# current_integrator.net
KiCad netlist of a schematic drawn in Altium Designer
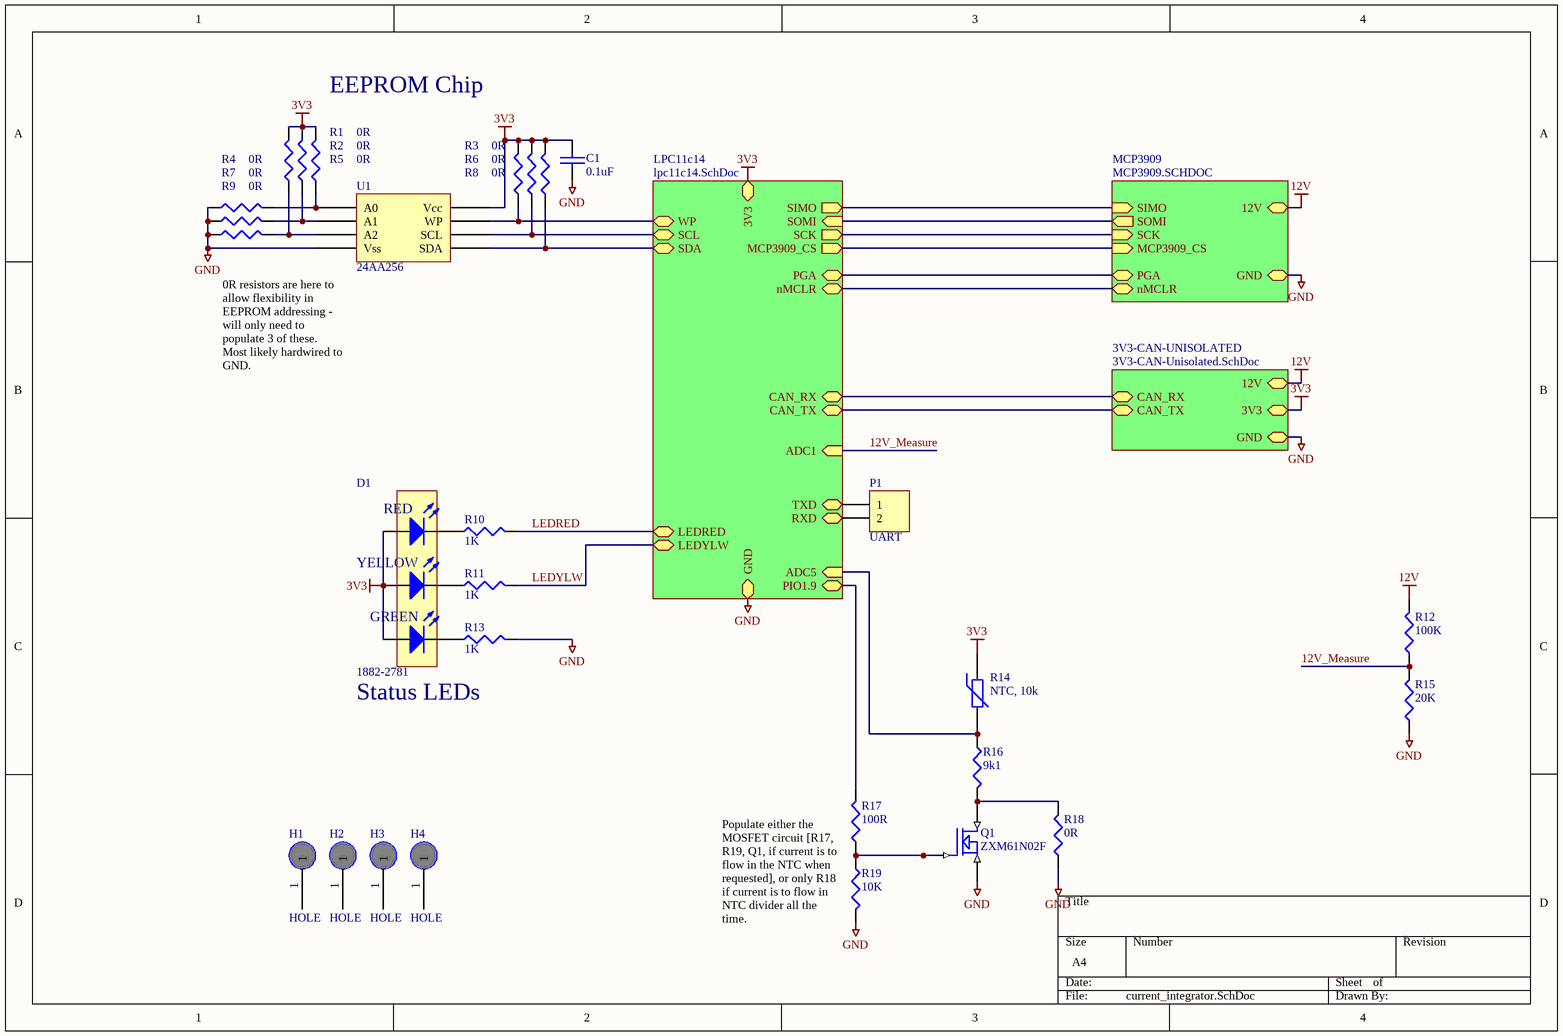
[diagram p0: current_integrator.SchDoc]

(export (version "E")
  (design (tool "Eeschema 10.0.6"))
  (components
    (comp (ref "C1")
      (value "0.1uF")
      (footprint "0805")
      (description "Capacitor")
      (libsource (lib "*") (part "CAP"))
    )
    (comp (ref "D1")
      (value "1882-2781")
      (footprint "LED_TRILEVEL")
      (description "Three level LED")
      (libsource (lib "RCLDQ") (part "LED-TRILEVEL"))
    )
    (comp (ref "H1")
      (value "HOLE")
      (footprint "M2.5")
      (description "Hole")
      (libsource (lib "Miscellaneous") (part "HOLE"))
    )
    (comp (ref "H2")
      (value "HOLE")
      (footprint "M2.5")
      (description "Hole")
      (libsource (lib "Miscellaneous") (part "HOLE"))
    )
    (comp (ref "H3")
      (value "HOLE")
      (footprint "M2.5")
      (description "Hole")
      (libsource (lib "Miscellaneous") (part "HOLE"))
    )
    (comp (ref "H4")
      (value "HOLE")
      (footprint "M2.5")
      (description "Hole")
      (libsource (lib "Miscellaneous") (part "HOLE"))
    )
    (comp (ref "P1")
      (value "UART")
      (footprint "HDR1X2")
      (description "Header, 2-Pin")
      (fields (field (name "PUBLISHER") "Altium Limited"))
      (libsource (lib "Miscellaneous Connectors") (part "Header 2"))
    )
    (comp (ref "Q1")
      (value "ZXM61N02F")
      (footprint "SOT23-3")
      (description "1.7A, 20V N-Channel Enhancement mode FET")
      (libsource (lib "RCLDQ") (part "ZXM61N02F"))
    )
    (comp (ref "R1")
      (value "0R")
      (footprint "0603")
      (description "Resistor")
      (libsource (lib "SunswiftLib20030312RR") (part "RES1"))
    )
    (comp (ref "R2")
      (value "0R")
      (footprint "0603")
      (description "Resistor")
      (libsource (lib "SunswiftLib20030312RR") (part "RES1"))
    )
    (comp (ref "R3")
      (value "0R")
      (footprint "0603")
      (description "Resistor")
      (libsource (lib "SunswiftLib20030312RR") (part "RES1"))
    )
    (comp (ref "R4")
      (value "0R")
      (footprint "0603")
      (description "Resistor")
      (libsource (lib "SunswiftLib20030312RR") (part "RES1"))
    )
    (comp (ref "R5")
      (value "0R")
      (footprint "0603")
      (description "Resistor")
      (libsource (lib "SunswiftLib20030312RR") (part "RES1"))
    )
    (comp (ref "R6")
      (value "0R")
      (footprint "0603")
      (description "Resistor")
      (libsource (lib "SunswiftLib20030312RR") (part "RES1"))
    )
    (comp (ref "R7")
      (value "0R")
      (footprint "0603")
      (description "Resistor")
      (libsource (lib "SunswiftLib20030312RR") (part "RES1"))
    )
    (comp (ref "R8")
      (value "0R")
      (footprint "0603")
      (description "Resistor")
      (libsource (lib "SunswiftLib20030312RR") (part "RES1"))
    )
    (comp (ref "R9")
      (value "0R")
      (footprint "0603")
      (description "Resistor")
      (libsource (lib "SunswiftLib20030312RR") (part "RES1"))
    )
    (comp (ref "R10")
      (value "1K")
      (footprint "0603")
      (description "Resistor")
      (libsource (lib "RCLDQ") (part "RES1"))
    )
    (comp (ref "R11")
      (value "1K")
      (footprint "0603")
      (description "Resistor")
      (libsource (lib "RCLDQ") (part "RES1"))
    )
    (comp (ref "R12")
      (value "100K")
      (footprint "1206")
      (description "Resistor")
      (libsource (lib "2009_BatteryMaster") (part "RES1"))
    )
    (comp (ref "R13")
      (value "1K")
      (footprint "0603")
      (description "Resistor")
      (libsource (lib "RCLDQ") (part "RES1"))
    )
    (comp (ref "R14")
      (value "NTC, 10k")
      (footprint "NTC_EPCOS")
      (description "Varistor (Voltage-Sensitive Resistor)")
      (libsource (lib "Miscellaneous Devices") (part "Res Varistor"))
    )
    (comp (ref "R15")
      (value "20K")
      (footprint "1206")
      (description "Resistor")
      (libsource (lib "2009_BatteryMaster") (part "RES1"))
    )
    (comp (ref "R16")
      (value "9k1")
      (footprint "0603")
      (description "Resistor")
      (libsource (lib "SUNSWIFTLIB") (part "RES1"))
    )
    (comp (ref "R17")
      (value "100R")
      (footprint "0603")
      (description "Resistor")
      (libsource (lib "SUNSWIFTLIB") (part "RES1"))
    )
    (comp (ref "R18")
      (value "0R")
      (footprint "0603")
      (description "Resistor")
      (libsource (lib "SUNSWIFTLIB") (part "RES1"))
    )
    (comp (ref "R19")
      (value "10K")
      (footprint "0603")
      (description "Resistor")
      (libsource (lib "SUNSWIFTLIB") (part "RES1"))
    )
    (comp (ref "U1") (value "24AA256") (footprint "DIP8") (libsource (lib "Miscellaneous") (part "24AA256")))
  )
  (nets
    (net (code "1") (name "/12V_Measure") (class "Default")
      (node (ref "R12") (pin "1") (pinfunction "1_1") (pintype "passive"))
      (node (ref "R15") (pin "2") (pinfunction "2_2") (pintype "passive"))
    )
    (net (code "2") (name "/ADC5") (class "Default")
      (node (ref "R14") (pin "2") (pinfunction "2_2") (pintype "passive"))
      (node (ref "R16") (pin "1") (pinfunction "1_1") (pintype "passive"))
    )
    (net (code "5") (name "/LEDRED") (class "Default")
      (node (ref "R10") (pin "2") (pinfunction "2_2") (pintype "passive"))
    )
    (net (code "6") (name "/LEDYLW") (class "Default")
      (node (ref "R11") (pin "2") (pinfunction "2_2") (pintype "passive"))
    )
    (net (code "9") (name "/PIO1.9") (class "Default")
      (node (ref "R17") (pin "2") (pinfunction "2_2") (pintype "passive"))
    )
    (net (code "10") (name "/RXD") (class "Default")
      (node (ref "P1") (pin "2") (pinfunction "2_2") (pintype "passive"))
    )
    (net (code "12") (name "/SCL") (class "Default")
      (node (ref "R6") (pin "1") (pinfunction "1_1") (pintype "passive"))
      (node (ref "U1") (pin "6") (pinfunction "SCL_6") (pintype "passive"))
    )
    (net (code "13") (name "/SDA") (class "Default")
      (node (ref "R3") (pin "1") (pinfunction "1_1") (pintype "passive"))
      (node (ref "U1") (pin "5") (pinfunction "SDA_5") (pintype "passive"))
    )
    (net (code "16") (name "/TXD") (class "Default")
      (node (ref "P1") (pin "1") (pinfunction "1_1") (pintype "passive"))
    )
    (net (code "17") (name "/WP") (class "Default")
      (node (ref "R8") (pin "1") (pinfunction "1_1") (pintype "passive"))
      (node (ref "U1") (pin "7") (pinfunction "WP_7") (pintype "passive"))
    )
    (net (code "19") (name "3V3") (class "Default")
      (node (ref "C1") (pin "1") (pinfunction "1_1") (pintype "passive"))
      (node (ref "D1") (pin "4") (pinfunction "A_4") (pintype "passive"))
      (node (ref "D1") (pin "5") (pinfunction "A_5") (pintype "passive"))
      (node (ref "D1") (pin "6") (pinfunction "A_6") (pintype "passive"))
      (node (ref "R1") (pin "2") (pinfunction "2_2") (pintype "passive"))
      (node (ref "R14") (pin "1") (pinfunction "1_1") (pintype "passive"))
      (node (ref "R2") (pin "2") (pinfunction "2_2") (pintype "passive"))
      (node (ref "R3") (pin "2") (pinfunction "2_2") (pintype "passive"))
      (node (ref "R5") (pin "2") (pinfunction "2_2") (pintype "passive"))
      (node (ref "R6") (pin "2") (pinfunction "2_2") (pintype "passive"))
      (node (ref "R8") (pin "2") (pinfunction "2_2") (pintype "passive"))
      (node (ref "U1") (pin "8") (pinfunction "Vcc_8") (pintype "passive"))
    )
    (net (code "20") (name "12V") (class "Default")
      (node (ref "R12") (pin "2") (pinfunction "2_2") (pintype "passive"))
    )
    (net (code "21") (name "GND") (class "Default")
      (node (ref "C1") (pin "2") (pinfunction "2_2") (pintype "passive"))
      (node (ref "Q1") (pin "2") (pinfunction "S_2") (pintype "input"))
      (node (ref "R13") (pin "2") (pinfunction "2_2") (pintype "passive"))
      (node (ref "R15") (pin "1") (pinfunction "1_1") (pintype "passive"))
      (node (ref "R18") (pin "1") (pinfunction "1_1") (pintype "passive"))
      (node (ref "R19") (pin "2") (pinfunction "2_2") (pintype "passive"))
      (node (ref "R4") (pin "1") (pinfunction "1_1") (pintype "passive"))
      (node (ref "R7") (pin "1") (pinfunction "1_1") (pintype "passive"))
      (node (ref "R9") (pin "1") (pinfunction "1_1") (pintype "passive"))
      (node (ref "U1") (pin "4") (pinfunction "Vss_4") (pintype "passive"))
    )
    (net (code "22") (name "Net-(D1-K-Pad1)") (class "Default")
      (node (ref "D1") (pin "1") (pinfunction "K_1") (pintype "passive"))
      (node (ref "R13") (pin "1") (pinfunction "1_1") (pintype "passive"))
    )
    (net (code "23") (name "Net-(D1-K-Pad2)") (class "Default")
      (node (ref "D1") (pin "2") (pinfunction "K_2") (pintype "passive"))
      (node (ref "R11") (pin "1") (pinfunction "1_1") (pintype "passive"))
    )
    (net (code "24") (name "Net-(D1-K-Pad3)") (class "Default")
      (node (ref "D1") (pin "3") (pinfunction "K_3") (pintype "passive"))
      (node (ref "R10") (pin "1") (pinfunction "1_1") (pintype "passive"))
    )
    (net (code "25") (name "Net-(Q1-D)") (class "Default")
      (node (ref "Q1") (pin "3") (pinfunction "D_3") (pintype "input"))
      (node (ref "R16") (pin "2") (pinfunction "2_2") (pintype "passive"))
      (node (ref "R18") (pin "2") (pinfunction "2_2") (pintype "passive"))
    )
    (net (code "26") (name "Net-(Q1-G)") (class "Default")
      (node (ref "Q1") (pin "1") (pinfunction "G_1") (pintype "input"))
      (node (ref "R17") (pin "1") (pinfunction "1_1") (pintype "passive"))
      (node (ref "R19") (pin "1") (pinfunction "1_1") (pintype "passive"))
    )
    (net (code "27") (name "Net-(U1-A0)") (class "Default")
      (node (ref "R1") (pin "1") (pinfunction "1_1") (pintype "passive"))
      (node (ref "R4") (pin "2") (pinfunction "2_2") (pintype "passive"))
      (node (ref "U1") (pin "1") (pinfunction "A0_1") (pintype "passive"))
    )
    (net (code "28") (name "Net-(U1-A1)") (class "Default")
      (node (ref "R2") (pin "1") (pinfunction "1_1") (pintype "passive"))
      (node (ref "R7") (pin "2") (pinfunction "2_2") (pintype "passive"))
      (node (ref "U1") (pin "2") (pinfunction "A1_2") (pintype "passive"))
    )
    (net (code "29") (name "Net-(U1-A2)") (class "Default")
      (node (ref "R5") (pin "1") (pinfunction "1_1") (pintype "passive"))
      (node (ref "R9") (pin "2") (pinfunction "2_2") (pintype "passive"))
      (node (ref "U1") (pin "3") (pinfunction "A2_3") (pintype "passive"))
    )
    (net (code "30") (name "unconnected-(H1-Pad1)") (class "Default")
      (node (ref "H1") (pin "1") (pinfunction "1_1") (pintype "passive"))
    )
    (net (code "31") (name "unconnected-(H2-Pad1)") (class "Default")
      (node (ref "H2") (pin "1") (pinfunction "1_1") (pintype "passive"))
    )
    (net (code "32") (name "unconnected-(H3-Pad1)") (class "Default")
      (node (ref "H3") (pin "1") (pinfunction "1_1") (pintype "passive"))
    )
    (net (code "33") (name "unconnected-(H4-Pad1)") (class "Default")
      (node (ref "H4") (pin "1") (pinfunction "1_1") (pintype "passive"))
    )
  )
)
